# IO_Buffer_SN74AHCT541.net
KiCad netlist of a schematic drawn in Altium Designer
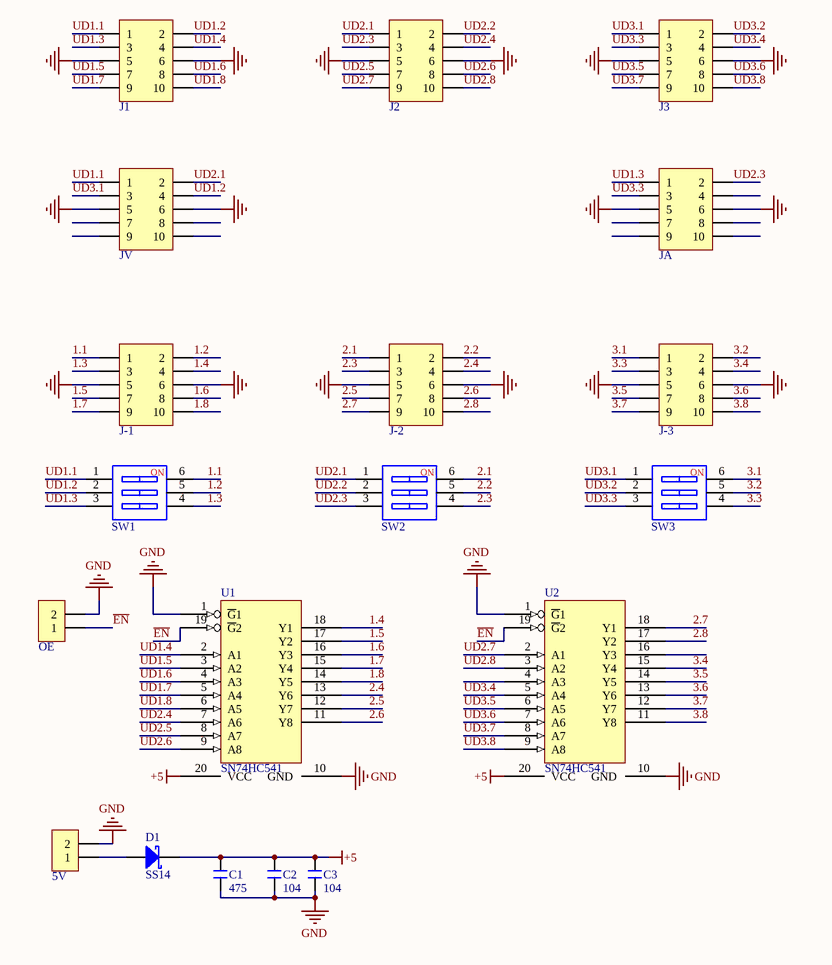
[diagram p0: IO_Buffer_SN74AHCT541.SchDoc]

(export (version "E")
  (design (tool "Eeschema 10.0.6"))
  (components
    (comp (ref "5V")
      (value "HDR-1X2")
      (footprint "HDR2.54-LI-2P")
      (description "2P接插件")
      (libsource (lib "18 - 接插件-脚距2.54mm (100mil) ") (part "Header 2"))
    )
    (comp (ref "C1")
      (value "475")
      (footprint "C 0805_L")
      (description "贴片电容")
      (libsource (lib "01 - 电容-电阻-电感") (part "C"))
    )
    (comp (ref "C2")
      (value "104")
      (footprint "C 0805_L")
      (description "贴片电容")
      (libsource (lib "01 - 电容-电阻-电感") (part "C"))
    )
    (comp (ref "C3")
      (value "104")
      (footprint "C 0805_L")
      (description "贴片电容")
      (libsource (lib "01 - 电容-电阻-电感") (part "C"))
    )
    (comp (ref "D1")
      (value "SS14")
      (footprint "SMA")
      (description "肖特基二极管")
      (libsource (lib "02 - 二极管(LED)-三极管-整流桥") (part "SS14"))
    )
    (comp (ref "J-1")
      (value "Header 5X2")
      (footprint "IDC2.54-LI-2x5P")
      (description "5*2P接插件")
      (libsource (lib "18 - 接插件-脚距2.54mm (100mil) ") (part "Header 5X2"))
    )
    (comp (ref "J-2")
      (value "Header 5X2")
      (footprint "IDC2.54-LI-2x5P")
      (description "5*2P接插件")
      (libsource (lib "18 - 接插件-脚距2.54mm (100mil) ") (part "Header 5X2"))
    )
    (comp (ref "J-3")
      (value "Header 5X2")
      (footprint "IDC2.54-LI-2x5P")
      (description "5*2P接插件")
      (libsource (lib "18 - 接插件-脚距2.54mm (100mil) ") (part "Header 5X2"))
    )
    (comp (ref "J1")
      (value "Header 5X2")
      (footprint "HDR2.54-LI-2x5P")
      (description "5*2P接插件")
      (libsource (lib "18 - 接插件-脚距2.54mm (100mil) ") (part "Header 5X2"))
    )
    (comp (ref "J2")
      (value "Header 5X2")
      (footprint "HDR2.54-LI-2x5P")
      (description "5*2P接插件")
      (libsource (lib "18 - 接插件-脚距2.54mm (100mil) ") (part "Header 5X2"))
    )
    (comp (ref "J3")
      (value "Header 5X2")
      (footprint "HDR2.54-LI-2x5P")
      (description "5*2P接插件")
      (libsource (lib "18 - 接插件-脚距2.54mm (100mil) ") (part "Header 5X2"))
    )
    (comp (ref "JA")
      (value "Header 5X2")
      (footprint "IDC2.54-LI-2x5P")
      (description "5*2P接插件")
      (libsource (lib "18 - 接插件-脚距2.54mm (100mil) ") (part "Header 5X2"))
    )
    (comp (ref "JV")
      (value "Header 5X2")
      (footprint "IDC2.54-LI-2x5P")
      (description "5*2P接插件")
      (libsource (lib "18 - 接插件-脚距2.54mm (100mil) ") (part "Header 5X2"))
    )
    (comp (ref "OE")
      (value "HDR-1X2")
      (footprint "HDR2.54-LI-2P")
      (description "2P接插件")
      (libsource (lib "18 - 接插件-脚距2.54mm (100mil) ") (part "Header 2"))
    )
    (comp (ref "SW1")
      (value "SW-3P")
      (footprint "CSW DIP-3P")
      (description "3路编码开关")
      (libsource (lib "03 - 按键-开关-晶振-蜂鸣器") (part "SW-3P"))
    )
    (comp (ref "SW2")
      (value "SW-3P")
      (footprint "CSW DIP-3P")
      (description "3路编码开关")
      (libsource (lib "03 - 按键-开关-晶振-蜂鸣器") (part "SW-3P"))
    )
    (comp (ref "SW3")
      (value "SW-3P")
      (footprint "CSW DIP-3P")
      (description "3路编码开关")
      (libsource (lib "03 - 按键-开关-晶振-蜂鸣器") (part "SW-3P"))
    )
    (comp (ref "U1")
      (value "SN74HC541")
      (footprint "TSSOP20_N")
      (description "OCTAL BUF AND LINE DRV 3SO")
      (libsource (lib "34 - 74系列芯片") (part "SN74HC541"))
    )
    (comp (ref "U2")
      (value "SN74HC541")
      (footprint "TSSOP20_N")
      (description "OCTAL BUF AND LINE DRV 3SO")
      (libsource (lib "34 - 74系列芯片") (part "SN74HC541"))
    )
  )
  (nets
    (net (code "1") (name "+5") (class "Default")
      (node (ref "C1") (pin "2") (pinfunction "2_2") (pintype "passive"))
      (node (ref "C2") (pin "2") (pinfunction "2_2") (pintype "passive"))
      (node (ref "C3") (pin "2") (pinfunction "2_2") (pintype "passive"))
      (node (ref "D1") (pin "2") (pinfunction "K_2") (pintype "passive"))
      (node (ref "U1") (pin "20") (pinfunction "VCC_20") (pintype "power_in"))
      (node (ref "U2") (pin "20") (pinfunction "VCC_20") (pintype "power_in"))
    )
    (net (code "2") (name "/1.1") (class "Default")
      (node (ref "J-1") (pin "1") (pinfunction "1_1") (pintype "passive"))
      (node (ref "SW1") (pin "6") (pinfunction "6_6") (pintype "passive"))
    )
    (net (code "3") (name "/1.2") (class "Default")
      (node (ref "J-1") (pin "2") (pinfunction "2_2") (pintype "passive"))
      (node (ref "SW1") (pin "5") (pinfunction "5_5") (pintype "passive"))
    )
    (net (code "4") (name "/1.3") (class "Default")
      (node (ref "J-1") (pin "3") (pinfunction "3_3") (pintype "passive"))
      (node (ref "SW1") (pin "4") (pinfunction "4_4") (pintype "passive"))
    )
    (net (code "5") (name "/1.4") (class "Default")
      (node (ref "J-1") (pin "4") (pinfunction "4_4") (pintype "passive"))
      (node (ref "U1") (pin "18") (pinfunction "Y1_18") (pintype "tri_state"))
    )
    (net (code "6") (name "/1.5") (class "Default")
      (node (ref "J-1") (pin "7") (pinfunction "7_7") (pintype "passive"))
      (node (ref "U1") (pin "17") (pinfunction "Y2_17") (pintype "tri_state"))
    )
    (net (code "7") (name "/1.6") (class "Default")
      (node (ref "J-1") (pin "8") (pinfunction "8_8") (pintype "passive"))
      (node (ref "U1") (pin "16") (pinfunction "Y3_16") (pintype "tri_state"))
    )
    (net (code "8") (name "/1.7") (class "Default")
      (node (ref "J-1") (pin "9") (pinfunction "9_9") (pintype "passive"))
      (node (ref "U1") (pin "15") (pinfunction "Y4_15") (pintype "tri_state"))
    )
    (net (code "9") (name "/1.8") (class "Default")
      (node (ref "J-1") (pin "10") (pinfunction "10_10") (pintype "passive"))
      (node (ref "U1") (pin "14") (pinfunction "Y5_14") (pintype "tri_state"))
    )
    (net (code "10") (name "/2.1") (class "Default")
      (node (ref "J-2") (pin "1") (pinfunction "1_1") (pintype "passive"))
      (node (ref "SW2") (pin "6") (pinfunction "6_6") (pintype "passive"))
    )
    (net (code "11") (name "/2.2") (class "Default")
      (node (ref "J-2") (pin "2") (pinfunction "2_2") (pintype "passive"))
      (node (ref "SW2") (pin "5") (pinfunction "5_5") (pintype "passive"))
    )
    (net (code "12") (name "/2.3") (class "Default")
      (node (ref "J-2") (pin "3") (pinfunction "3_3") (pintype "passive"))
      (node (ref "SW2") (pin "4") (pinfunction "4_4") (pintype "passive"))
    )
    (net (code "13") (name "/2.4") (class "Default")
      (node (ref "J-2") (pin "4") (pinfunction "4_4") (pintype "passive"))
      (node (ref "U1") (pin "13") (pinfunction "Y6_13") (pintype "tri_state"))
    )
    (net (code "14") (name "/2.5") (class "Default")
      (node (ref "J-2") (pin "7") (pinfunction "7_7") (pintype "passive"))
      (node (ref "U1") (pin "12") (pinfunction "Y7_12") (pintype "tri_state"))
    )
    (net (code "15") (name "/2.6") (class "Default")
      (node (ref "J-2") (pin "8") (pinfunction "8_8") (pintype "passive"))
      (node (ref "U1") (pin "11") (pinfunction "Y8_11") (pintype "tri_state"))
    )
    (net (code "16") (name "/2.7") (class "Default")
      (node (ref "J-2") (pin "9") (pinfunction "9_9") (pintype "passive"))
      (node (ref "U2") (pin "18") (pinfunction "Y1_18") (pintype "tri_state"))
    )
    (net (code "17") (name "/2.8") (class "Default")
      (node (ref "J-2") (pin "10") (pinfunction "10_10") (pintype "passive"))
      (node (ref "U2") (pin "17") (pinfunction "Y2_17") (pintype "tri_state"))
    )
    (net (code "18") (name "/3.1") (class "Default")
      (node (ref "J-3") (pin "1") (pinfunction "1_1") (pintype "passive"))
      (node (ref "SW3") (pin "6") (pinfunction "6_6") (pintype "passive"))
    )
    (net (code "19") (name "/3.2") (class "Default")
      (node (ref "J-3") (pin "2") (pinfunction "2_2") (pintype "passive"))
      (node (ref "SW3") (pin "5") (pinfunction "5_5") (pintype "passive"))
    )
    (net (code "20") (name "/3.3") (class "Default")
      (node (ref "J-3") (pin "3") (pinfunction "3_3") (pintype "passive"))
      (node (ref "SW3") (pin "4") (pinfunction "4_4") (pintype "passive"))
    )
    (net (code "21") (name "/3.4") (class "Default")
      (node (ref "J-3") (pin "4") (pinfunction "4_4") (pintype "passive"))
      (node (ref "U2") (pin "15") (pinfunction "Y4_15") (pintype "tri_state"))
    )
    (net (code "22") (name "/3.5") (class "Default")
      (node (ref "J-3") (pin "7") (pinfunction "7_7") (pintype "passive"))
      (node (ref "U2") (pin "14") (pinfunction "Y5_14") (pintype "tri_state"))
    )
    (net (code "23") (name "/3.6") (class "Default")
      (node (ref "J-3") (pin "8") (pinfunction "8_8") (pintype "passive"))
      (node (ref "U2") (pin "13") (pinfunction "Y6_13") (pintype "tri_state"))
    )
    (net (code "24") (name "/3.7") (class "Default")
      (node (ref "J-3") (pin "9") (pinfunction "9_9") (pintype "passive"))
      (node (ref "U2") (pin "12") (pinfunction "Y7_12") (pintype "tri_state"))
    )
    (net (code "25") (name "/3.8") (class "Default")
      (node (ref "J-3") (pin "10") (pinfunction "10_10") (pintype "passive"))
      (node (ref "U2") (pin "11") (pinfunction "Y8_11") (pintype "tri_state"))
    )
    (net (code "26") (name "/UD1.1") (class "Default")
      (node (ref "J1") (pin "1") (pinfunction "1_1") (pintype "passive"))
      (node (ref "JV") (pin "1") (pinfunction "1_1") (pintype "passive"))
      (node (ref "SW1") (pin "1") (pinfunction "1_1") (pintype "passive"))
    )
    (net (code "27") (name "/UD1.2") (class "Default")
      (node (ref "J1") (pin "2") (pinfunction "2_2") (pintype "passive"))
      (node (ref "JV") (pin "4") (pinfunction "4_4") (pintype "passive"))
      (node (ref "SW1") (pin "2") (pinfunction "2_2") (pintype "passive"))
    )
    (net (code "28") (name "/UD1.3") (class "Default")
      (node (ref "J1") (pin "3") (pinfunction "3_3") (pintype "passive"))
      (node (ref "JA") (pin "1") (pinfunction "1_1") (pintype "passive"))
      (node (ref "SW1") (pin "3") (pinfunction "3_3") (pintype "passive"))
    )
    (net (code "29") (name "/UD1.4") (class "Default")
      (node (ref "J1") (pin "4") (pinfunction "4_4") (pintype "passive"))
      (node (ref "U1") (pin "2") (pinfunction "A1_2") (pintype "input"))
    )
    (net (code "30") (name "/UD1.5") (class "Default")
      (node (ref "J1") (pin "7") (pinfunction "7_7") (pintype "passive"))
      (node (ref "U1") (pin "3") (pinfunction "A2_3") (pintype "input"))
    )
    (net (code "31") (name "/UD1.6") (class "Default")
      (node (ref "J1") (pin "8") (pinfunction "8_8") (pintype "passive"))
      (node (ref "U1") (pin "4") (pinfunction "A3_4") (pintype "input"))
    )
    (net (code "32") (name "/UD1.7") (class "Default")
      (node (ref "J1") (pin "9") (pinfunction "9_9") (pintype "passive"))
      (node (ref "U1") (pin "5") (pinfunction "A4_5") (pintype "input"))
    )
    (net (code "33") (name "/UD1.8") (class "Default")
      (node (ref "J1") (pin "10") (pinfunction "10_10") (pintype "passive"))
      (node (ref "U1") (pin "6") (pinfunction "A5_6") (pintype "input"))
    )
    (net (code "34") (name "/UD2.1") (class "Default")
      (node (ref "J2") (pin "1") (pinfunction "1_1") (pintype "passive"))
      (node (ref "JV") (pin "2") (pinfunction "2_2") (pintype "passive"))
      (node (ref "SW2") (pin "1") (pinfunction "1_1") (pintype "passive"))
    )
    (net (code "35") (name "/UD2.2") (class "Default")
      (node (ref "J2") (pin "2") (pinfunction "2_2") (pintype "passive"))
      (node (ref "SW2") (pin "2") (pinfunction "2_2") (pintype "passive"))
    )
    (net (code "36") (name "/UD2.3") (class "Default")
      (node (ref "J2") (pin "3") (pinfunction "3_3") (pintype "passive"))
      (node (ref "JA") (pin "2") (pinfunction "2_2") (pintype "passive"))
      (node (ref "SW2") (pin "3") (pinfunction "3_3") (pintype "passive"))
    )
    (net (code "37") (name "/UD2.4") (class "Default")
      (node (ref "J2") (pin "4") (pinfunction "4_4") (pintype "passive"))
      (node (ref "U1") (pin "7") (pinfunction "A6_7") (pintype "input"))
    )
    (net (code "38") (name "/UD2.5") (class "Default")
      (node (ref "J2") (pin "7") (pinfunction "7_7") (pintype "passive"))
      (node (ref "U1") (pin "8") (pinfunction "A7_8") (pintype "input"))
    )
    (net (code "39") (name "/UD2.6") (class "Default")
      (node (ref "J2") (pin "8") (pinfunction "8_8") (pintype "passive"))
      (node (ref "U1") (pin "9") (pinfunction "A8_9") (pintype "input"))
    )
    (net (code "40") (name "/UD2.7") (class "Default")
      (node (ref "J2") (pin "9") (pinfunction "9_9") (pintype "passive"))
      (node (ref "U2") (pin "2") (pinfunction "A1_2") (pintype "input"))
    )
    (net (code "41") (name "/UD2.8") (class "Default")
      (node (ref "J2") (pin "10") (pinfunction "10_10") (pintype "passive"))
      (node (ref "U2") (pin "3") (pinfunction "A2_3") (pintype "input"))
    )
    (net (code "42") (name "/UD3.1") (class "Default")
      (node (ref "J3") (pin "1") (pinfunction "1_1") (pintype "passive"))
      (node (ref "JV") (pin "3") (pinfunction "3_3") (pintype "passive"))
      (node (ref "SW3") (pin "1") (pinfunction "1_1") (pintype "passive"))
    )
    (net (code "43") (name "/UD3.2") (class "Default")
      (node (ref "J3") (pin "2") (pinfunction "2_2") (pintype "passive"))
      (node (ref "SW3") (pin "2") (pinfunction "2_2") (pintype "passive"))
    )
    (net (code "44") (name "/UD3.3") (class "Default")
      (node (ref "J3") (pin "3") (pinfunction "3_3") (pintype "passive"))
      (node (ref "JA") (pin "3") (pinfunction "3_3") (pintype "passive"))
      (node (ref "SW3") (pin "3") (pinfunction "3_3") (pintype "passive"))
    )
    (net (code "45") (name "/UD3.4") (class "Default")
      (node (ref "J3") (pin "4") (pinfunction "4_4") (pintype "passive"))
      (node (ref "U2") (pin "5") (pinfunction "A4_5") (pintype "input"))
    )
    (net (code "46") (name "/UD3.5") (class "Default")
      (node (ref "J3") (pin "7") (pinfunction "7_7") (pintype "passive"))
      (node (ref "U2") (pin "6") (pinfunction "A5_6") (pintype "input"))
    )
    (net (code "47") (name "/UD3.6") (class "Default")
      (node (ref "J3") (pin "8") (pinfunction "8_8") (pintype "passive"))
      (node (ref "U2") (pin "7") (pinfunction "A6_7") (pintype "input"))
    )
    (net (code "48") (name "/UD3.7") (class "Default")
      (node (ref "J3") (pin "9") (pinfunction "9_9") (pintype "passive"))
      (node (ref "U2") (pin "8") (pinfunction "A7_8") (pintype "input"))
    )
    (net (code "49") (name "/UD3.8") (class "Default")
      (node (ref "J3") (pin "10") (pinfunction "10_10") (pintype "passive"))
      (node (ref "U2") (pin "9") (pinfunction "A8_9") (pintype "input"))
    )
    (net (code "50") (name "/~{EN}") (class "Default")
      (node (ref "OE") (pin "1") (pinfunction "1_1") (pintype "passive"))
      (node (ref "U1") (pin "19") (pinfunction "~{G}2_19") (pintype "input"))
      (node (ref "U2") (pin "19") (pinfunction "~{G}2_19") (pintype "input"))
    )
    (net (code "51") (name "GND") (class "Default")
      (node (ref "5V") (pin "2") (pinfunction "2_2") (pintype "passive"))
      (node (ref "C1") (pin "1") (pinfunction "1_1") (pintype "passive"))
      (node (ref "C2") (pin "1") (pinfunction "1_1") (pintype "passive"))
      (node (ref "C3") (pin "1") (pinfunction "1_1") (pintype "passive"))
      (node (ref "J-1") (pin "5") (pinfunction "5_5") (pintype "passive"))
      (node (ref "J-1") (pin "6") (pinfunction "6_6") (pintype "passive"))
      (node (ref "J-2") (pin "5") (pinfunction "5_5") (pintype "passive"))
      (node (ref "J-2") (pin "6") (pinfunction "6_6") (pintype "passive"))
      (node (ref "J-3") (pin "5") (pinfunction "5_5") (pintype "passive"))
      (node (ref "J-3") (pin "6") (pinfunction "6_6") (pintype "passive"))
      (node (ref "J1") (pin "5") (pinfunction "5_5") (pintype "passive"))
      (node (ref "J1") (pin "6") (pinfunction "6_6") (pintype "passive"))
      (node (ref "J2") (pin "5") (pinfunction "5_5") (pintype "passive"))
      (node (ref "J2") (pin "6") (pinfunction "6_6") (pintype "passive"))
      (node (ref "J3") (pin "5") (pinfunction "5_5") (pintype "passive"))
      (node (ref "J3") (pin "6") (pinfunction "6_6") (pintype "passive"))
      (node (ref "JA") (pin "5") (pinfunction "5_5") (pintype "passive"))
      (node (ref "JA") (pin "6") (pinfunction "6_6") (pintype "passive"))
      (node (ref "JV") (pin "5") (pinfunction "5_5") (pintype "passive"))
      (node (ref "JV") (pin "6") (pinfunction "6_6") (pintype "passive"))
      (node (ref "OE") (pin "2") (pinfunction "2_2") (pintype "passive"))
      (node (ref "U1") (pin "1") (pinfunction "~{G}1_1") (pintype "input"))
      (node (ref "U1") (pin "10") (pinfunction "GND_10") (pintype "power_in"))
      (node (ref "U2") (pin "1") (pinfunction "~{G}1_1") (pintype "input"))
      (node (ref "U2") (pin "10") (pinfunction "GND_10") (pintype "power_in"))
    )
    (net (code "52") (name "Net-(D1-A)") (class "Default")
      (node (ref "5V") (pin "1") (pinfunction "1_1") (pintype "passive"))
      (node (ref "D1") (pin "1") (pinfunction "A_1") (pintype "passive"))
    )
    (net (code "53") (name "unconnected-(JA-Pad4)") (class "Default")
      (node (ref "JA") (pin "4") (pinfunction "4_4") (pintype "passive"))
    )
    (net (code "54") (name "unconnected-(JA-Pad7)") (class "Default")
      (node (ref "JA") (pin "7") (pinfunction "7_7") (pintype "passive"))
    )
    (net (code "55") (name "unconnected-(JA-Pad8)") (class "Default")
      (node (ref "JA") (pin "8") (pinfunction "8_8") (pintype "passive"))
    )
    (net (code "56") (name "unconnected-(JA-Pad9)") (class "Default")
      (node (ref "JA") (pin "9") (pinfunction "9_9") (pintype "passive"))
    )
    (net (code "57") (name "unconnected-(JA-Pad10)") (class "Default")
      (node (ref "JA") (pin "10") (pinfunction "10_10") (pintype "passive"))
    )
    (net (code "58") (name "unconnected-(JV-Pad7)") (class "Default")
      (node (ref "JV") (pin "7") (pinfunction "7_7") (pintype "passive"))
    )
    (net (code "59") (name "unconnected-(JV-Pad8)") (class "Default")
      (node (ref "JV") (pin "8") (pinfunction "8_8") (pintype "passive"))
    )
    (net (code "60") (name "unconnected-(JV-Pad9)") (class "Default")
      (node (ref "JV") (pin "9") (pinfunction "9_9") (pintype "passive"))
    )
    (net (code "61") (name "unconnected-(JV-Pad10)") (class "Default")
      (node (ref "JV") (pin "10") (pinfunction "10_10") (pintype "passive"))
    )
    (net (code "62") (name "unconnected-(U2-A3-Pad4)") (class "Default")
      (node (ref "U2") (pin "4") (pinfunction "A3_4") (pintype "input"))
    )
    (net (code "63") (name "unconnected-(U2-Y3-Pad16)") (class "Default")
      (node (ref "U2") (pin "16") (pinfunction "Y3_16") (pintype "tri_state"))
    )
  )
)
